# Buttons.net
KiCad netlist of a schematic drawn in Altium Designer
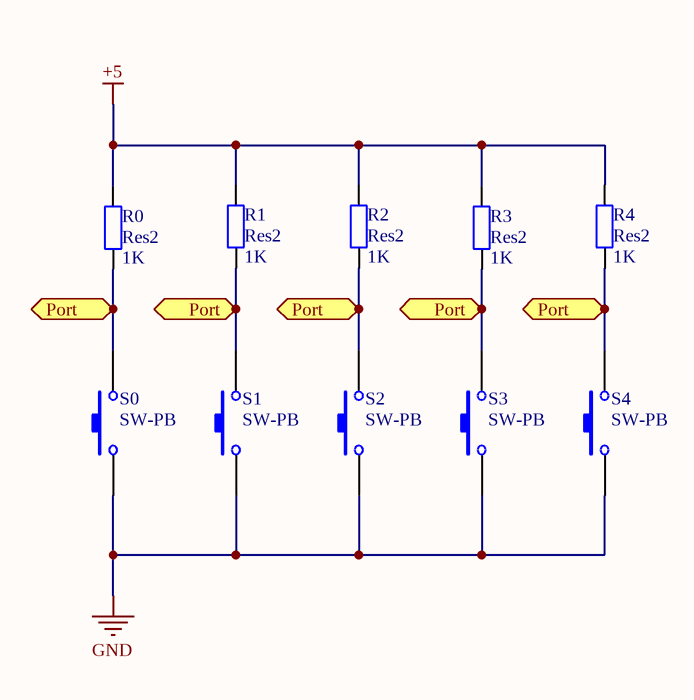
[diagram p0: Buttons.SchDoc]

(export (version "E")
  (design (tool "Eeschema 10.0.6"))
  (components
    (comp (ref "R0")
      (value "Res2")
      (footprint "AXIAL-0.4")
      (description "Resistor")
      (fields (field (name "ALTIUM_VALUE") "1K") (field (name "PUBLISHER") "Altium Limited"))
      (libsource (lib "Miscellaneous Devices") (part "Res2"))
    )
    (comp (ref "R1")
      (value "Res2")
      (footprint "AXIAL-0.4")
      (description "Resistor")
      (fields (field (name "ALTIUM_VALUE") "1K") (field (name "PUBLISHER") "Altium Limited"))
      (libsource (lib "Miscellaneous Devices") (part "Res2"))
    )
    (comp (ref "R2")
      (value "Res2")
      (footprint "AXIAL-0.4")
      (description "Resistor")
      (fields (field (name "ALTIUM_VALUE") "1K") (field (name "PUBLISHER") "Altium Limited"))
      (libsource (lib "Miscellaneous Devices") (part "Res2"))
    )
    (comp (ref "R3")
      (value "Res2")
      (footprint "AXIAL-0.4")
      (description "Resistor")
      (fields (field (name "ALTIUM_VALUE") "1K") (field (name "PUBLISHER") "Altium Limited"))
      (libsource (lib "Miscellaneous Devices") (part "Res2"))
    )
    (comp (ref "R4")
      (value "Res2")
      (footprint "AXIAL-0.4")
      (description "Resistor")
      (fields (field (name "ALTIUM_VALUE") "1K") (field (name "PUBLISHER") "Altium Limited"))
      (libsource (lib "") (part "Res2_1"))
    )
    (comp (ref "S0")
      (value "SW-PB")
      (footprint "SPST-2")
      (description "Switch")
      (fields (field (name "PUBLISHER") "Altium Limited"))
      (libsource (lib "Miscellaneous Devices") (part "SW-PB"))
    )
    (comp (ref "S1")
      (value "SW-PB")
      (footprint "SPST-2")
      (description "Switch")
      (fields (field (name "PUBLISHER") "Altium Limited"))
      (libsource (lib "Miscellaneous Devices") (part "SW-PB"))
    )
    (comp (ref "S2")
      (value "SW-PB")
      (footprint "SPST-2")
      (description "Switch")
      (fields (field (name "PUBLISHER") "Altium Limited"))
      (libsource (lib "Miscellaneous Devices") (part "SW-PB"))
    )
    (comp (ref "S3")
      (value "SW-PB")
      (footprint "SPST-2")
      (description "Switch")
      (fields (field (name "PUBLISHER") "Altium Limited"))
      (libsource (lib "Miscellaneous Devices") (part "SW-PB"))
    )
    (comp (ref "S4")
      (value "SW-PB")
      (footprint "SPST-2")
      (description "Switch")
      (fields (field (name "PUBLISHER") "Altium Limited"))
      (libsource (lib "Miscellaneous Devices") (part "SW-PB"))
    )
  )
  (nets
    (net (code "1") (name "+5") (class "Default")
      (node (ref "R0") (pin "2") (pinfunction "2_2") (pintype "passive"))
      (node (ref "R1") (pin "2") (pinfunction "2_2") (pintype "passive"))
      (node (ref "R2") (pin "2") (pinfunction "2_2") (pintype "passive"))
      (node (ref "R3") (pin "2") (pinfunction "2_2") (pintype "passive"))
      (node (ref "R4") (pin "1") (pinfunction "1_1") (pintype "passive"))
    )
    (net (code "2") (name "/Port") (class "Default")
      (node (ref "R0") (pin "1") (pinfunction "1_1") (pintype "passive"))
      (node (ref "R1") (pin "1") (pinfunction "1_1") (pintype "passive"))
      (node (ref "R2") (pin "1") (pinfunction "1_1") (pintype "passive"))
      (node (ref "R3") (pin "1") (pinfunction "1_1") (pintype "passive"))
      (node (ref "R4") (pin "2") (pinfunction "2_2") (pintype "passive"))
      (node (ref "S0") (pin "2") (pinfunction "2_2") (pintype "passive"))
      (node (ref "S1") (pin "2") (pinfunction "2_2") (pintype "passive"))
      (node (ref "S2") (pin "2") (pinfunction "2_2") (pintype "passive"))
      (node (ref "S3") (pin "2") (pinfunction "2_2") (pintype "passive"))
      (node (ref "S4") (pin "2") (pinfunction "2_2") (pintype "passive"))
    )
    (net (code "3") (name "GND") (class "Default")
      (node (ref "S0") (pin "1") (pinfunction "1_1") (pintype "passive"))
      (node (ref "S1") (pin "1") (pinfunction "1_1") (pintype "passive"))
      (node (ref "S2") (pin "1") (pinfunction "1_1") (pintype "passive"))
      (node (ref "S3") (pin "1") (pinfunction "1_1") (pintype "passive"))
      (node (ref "S4") (pin "1") (pinfunction "1_1") (pintype "passive"))
    )
  )
)
